# Lux_Meter.net
KiCad netlist of a schematic drawn in EAGLE
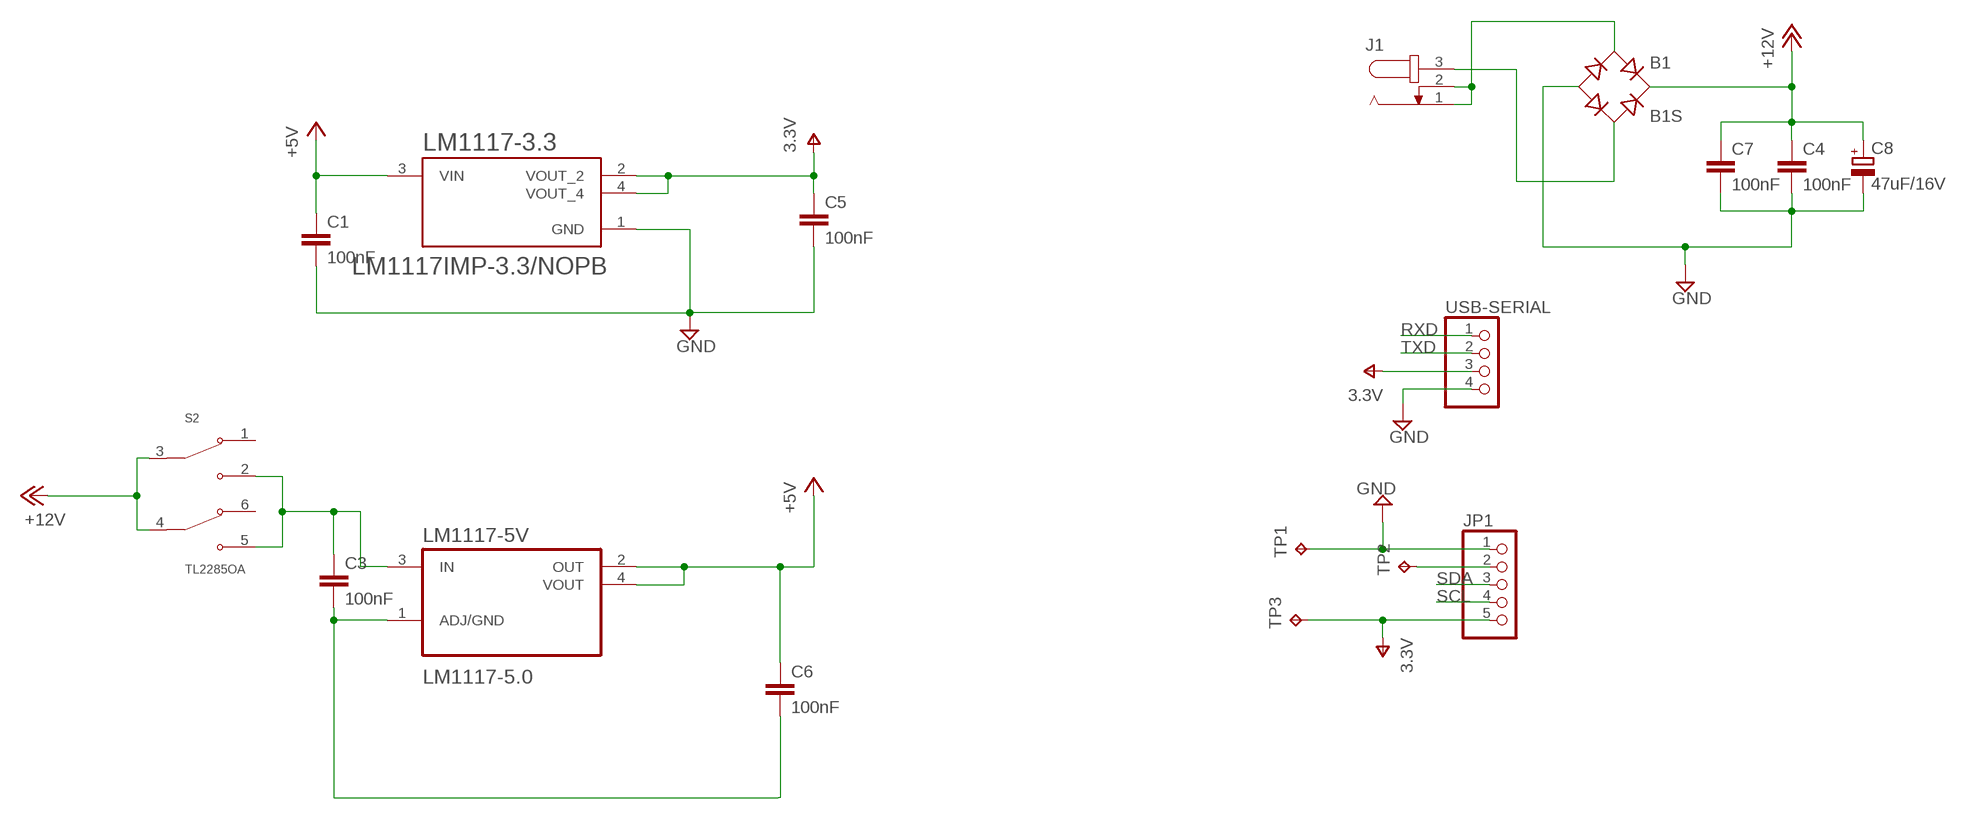
[diagram p0: schematic, sheet 1]
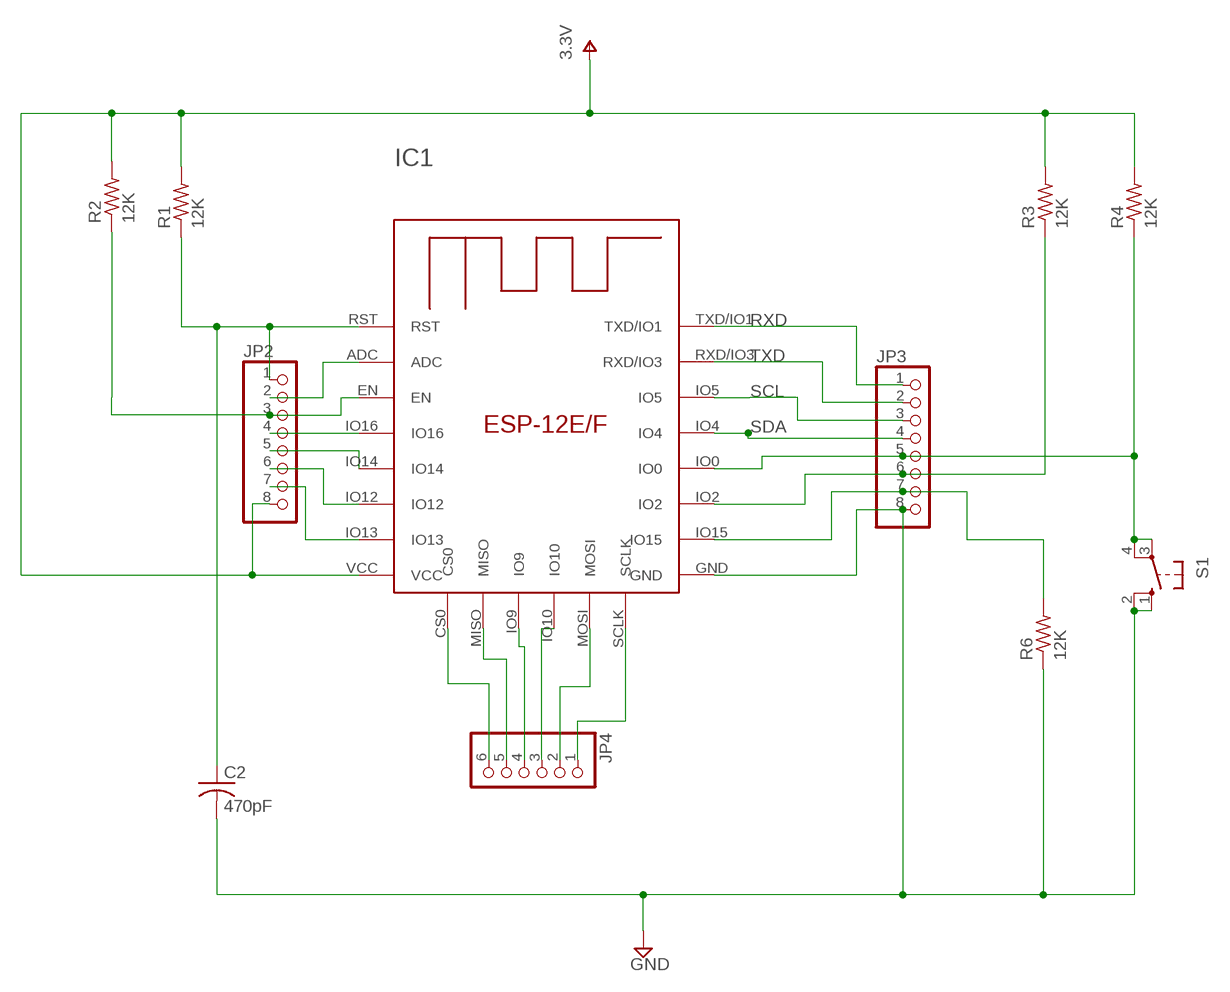
[diagram p1: schematic, sheet 2]

(export (version "E")
  (design (tool "Eeschema 10.0.6"))
  (components
    (comp (ref "C2")
      (value "470pF")
      (footprint "eagle-import:C0805")
      (libsource (lib "eagle-import") (part "C-USC0805"))
    )
    (comp (ref "IC1")
      (value "ESP-12E/F")
      (footprint "eagle-import:ESP-12E")
      (libsource (lib "eagle-import") (part "ESP-12E/F"))
    )
    (comp (ref "JP2")
      (value "PINHD-1X8")
      (footprint "eagle-import:1X08")
      (libsource (lib "eagle-import") (part "PINHD-1X8"))
    )
    (comp (ref "JP3")
      (value "PINHD-1X8")
      (footprint "eagle-import:1X08")
      (libsource (lib "eagle-import") (part "PINHD-1X8"))
    )
    (comp (ref "JP4")
      (value "PINHD-1X6")
      (footprint "eagle-import:1X06")
      (libsource (lib "eagle-import") (part "PINHD-1X6"))
    )
    (comp (ref "R1")
      (value "12K")
      (footprint "eagle-import:R0805")
      (libsource (lib "eagle-import") (part "R-US_R0805"))
    )
    (comp (ref "R2")
      (value "12K")
      (footprint "eagle-import:R0805")
      (libsource (lib "eagle-import") (part "R-US_R0805"))
    )
    (comp (ref "R3")
      (value "12K")
      (footprint "eagle-import:R0805")
      (libsource (lib "eagle-import") (part "R-US_R0805"))
    )
    (comp (ref "R4")
      (value "12K")
      (footprint "eagle-import:R0805")
      (libsource (lib "eagle-import") (part "R-US_R0805"))
    )
    (comp (ref "R6")
      (value "12K")
      (footprint "eagle-import:R0805")
      (libsource (lib "eagle-import") (part "R-US_R0805"))
    )
    (comp (ref "S1")
      (value "10-XX")
      (footprint "eagle-import:B3F-10XX")
      (fields (field (name "MPN") "B3F-1000"))
      (libsource (lib "eagle-import") (part "10-XX"))
    )
    (comp (ref "B1")
      (value "B1S")
      (footprint "eagle-import:MBS")
      (libsource (lib "eagle-import") (part "BS1"))
    )
    (comp (ref "C1")
      (value "100nF")
      (footprint "eagle-import:C0603K")
      (libsource (lib "eagle-import") (part "C-EUC0603K"))
    )
    (comp (ref "C3")
      (value "100nF")
      (footprint "eagle-import:C0603K")
      (libsource (lib "eagle-import") (part "C-EUC0603K"))
    )
    (comp (ref "C4")
      (value "100nF")
      (footprint "eagle-import:C0603K")
      (libsource (lib "eagle-import") (part "C-EUC0603K"))
    )
    (comp (ref "C5")
      (value "100nF")
      (footprint "eagle-import:C0805K")
      (libsource (lib "eagle-import") (part "C-EUC0805K"))
    )
    (comp (ref "C6")
      (value "100nF")
      (footprint "eagle-import:C0805K")
      (libsource (lib "eagle-import") (part "C-EUC0805K"))
    )
    (comp (ref "C7")
      (value "100nF")
      (footprint "eagle-import:C0805K")
      (libsource (lib "eagle-import") (part "C-EUC0805K"))
    )
    (comp (ref "C8")
      (value "47uF/16V")
      (footprint "eagle-import:C_6032-28R")
      (libsource (lib "eagle-import") (part "CPOL-EUC/6032-28R"))
    )
    (comp (ref "J1")
      (value "JACK-PLUG0")
      (footprint "eagle-import:SPC4077")
      (libsource (lib "eagle-import") (part "JACK-PLUG0"))
    )
    (comp (ref "JP1")
      (value "PINHD-1X5")
      (footprint "eagle-import:1X05")
      (libsource (lib "eagle-import") (part "PINHD-1X5"))
    )
    (comp (ref "LM1117-3.3")
      (value "LM1117IMP-3.3/NOPB")
      (footprint "eagle-import:VREG_LM1117IMP-3.3_NOPB")
      (fields (field (name "MF") "Texas"))
      (libsource (lib "eagle-import") (part "LM1117IMP-3.3/NOPB"))
    )
    (comp (ref "LM1117-5V")
      (value "LM1117-5.0")
      (footprint "eagle-import:SOT230P700X180-4N")
      (fields (field (name "MF") "Texas Instruments") (field (name "MP") "LM1117MP-5.0/NOPB"))
      (libsource (lib "eagle-import") (part "LM1117MP-5.0"))
    )
    (comp (ref "S2")
      (value "TL2285OA")
      (footprint "eagle-import:SW_TL2285OA")
      (fields (field (name "MF") "E-Switch"))
      (libsource (lib "eagle-import") (part "TL2285OA"))
    )
    (comp (ref "TP1")
      (value "TPTP13SQ")
      (footprint "eagle-import:TP13SQ")
      (libsource (lib "eagle-import") (part "TPTP13SQ"))
    )
    (comp (ref "TP2")
      (value "TPTP13SQ")
      (footprint "eagle-import:TP13SQ")
      (libsource (lib "eagle-import") (part "TPTP13SQ"))
    )
    (comp (ref "TP3")
      (value "TPTP13SQ")
      (footprint "eagle-import:TP13SQ")
      (libsource (lib "eagle-import") (part "TPTP13SQ"))
    )
    (comp (ref "USB-SERIAL")
      (value "PINHD-1X4")
      (footprint "eagle-import:1X04")
      (libsource (lib "eagle-import") (part "PINHD-1X4"))
    )
  )
  (nets
    (net (code "1") (name "+5V") (class "Default")
      (node (ref "C1") (pin "1") (pinfunction "1_1") (pintype "passive"))
      (node (ref "C6") (pin "1") (pinfunction "1_1") (pintype "passive"))
      (node (ref "LM1117-3.3") (pin "3") (pinfunction "VIN_3") (pintype "input"))
      (node (ref "LM1117-5V") (pin "2") (pinfunction "OUT_2") (pintype "output"))
      (node (ref "LM1117-5V") (pin "4") (pinfunction "VOUT_4") (pintype "output"))
    )
    (net (code "2") (name "+12V") (class "Default")
      (node (ref "B1") (pin "+") (pinfunction "+_+") (pintype "passive"))
      (node (ref "C4") (pin "1") (pinfunction "1_1") (pintype "passive"))
      (node (ref "C7") (pin "1") (pinfunction "1_1") (pintype "passive"))
      (node (ref "C8") (pin "+") (pinfunction "+_+") (pintype "passive"))
      (node (ref "S2") (pin "3") (pinfunction "COM1_3") (pintype "passive"))
      (node (ref "S2") (pin "4") (pinfunction "COM2_4") (pintype "passive"))
    )
    (net (code "3") (name "GND") (class "Default")
      (node (ref "B1") (pin "-") (pinfunction "-_-") (pintype "passive"))
      (node (ref "C1") (pin "2") (pinfunction "2_2") (pintype "passive"))
      (node (ref "C2") (pin "2") (pinfunction "2_2") (pintype "passive"))
      (node (ref "C4") (pin "2") (pinfunction "2_2") (pintype "passive"))
      (node (ref "C5") (pin "2") (pinfunction "2_2") (pintype "passive"))
      (node (ref "C7") (pin "2") (pinfunction "2_2") (pintype "passive"))
      (node (ref "C8") (pin "-") (pinfunction "-_-") (pintype "passive"))
      (node (ref "IC1") (pin "GND") (pinfunction "GND_GND") (pintype "power_in"))
      (node (ref "JP1") (pin "1") (pinfunction "1_1") (pintype "passive"))
      (node (ref "JP3") (pin "8") (pinfunction "8_8") (pintype "passive"))
      (node (ref "LM1117-3.3") (pin "1") (pinfunction "GND_1") (pintype "power_in"))
      (node (ref "R6") (pin "1") (pinfunction "1_1") (pintype "passive"))
      (node (ref "S1") (pin "1") (pinfunction "S_1") (pintype "passive"))
      (node (ref "S1") (pin "2") (pinfunction "S1_2") (pintype "passive"))
      (node (ref "TP1") (pin "TP") (pinfunction "TP_TP") (pintype "input"))
      (node (ref "USB-SERIAL") (pin "4") (pinfunction "4_4") (pintype "passive"))
    )
    (net (code "4") (name "Net-(B1-PadAC1)") (class "Default")
      (node (ref "B1") (pin "AC1") (pinfunction "AC1_AC1") (pintype "passive"))
      (node (ref "J1") (pin "1") (pinfunction "1_1") (pintype "passive"))
      (node (ref "J1") (pin "2") (pinfunction "2_2") (pintype "passive"))
    )
    (net (code "5") (name "Net-(B1-PadAC2)") (class "Default")
      (node (ref "B1") (pin "AC2") (pinfunction "AC2_AC2") (pintype "passive"))
      (node (ref "J1") (pin "3") (pinfunction "3_3") (pintype "passive"))
    )
    (net (code "6") (name "Net-(C2-Pad1)") (class "Default")
      (node (ref "C2") (pin "1") (pinfunction "1_1") (pintype "passive"))
      (node (ref "IC1") (pin "RST") (pinfunction "RST_RST") (pintype "input"))
      (node (ref "JP2") (pin "1") (pinfunction "1_1") (pintype "passive"))
      (node (ref "R1") (pin "1") (pinfunction "1_1") (pintype "passive"))
    )
    (net (code "7") (name "Net-(IC1-PadADC)") (class "Default")
      (node (ref "IC1") (pin "ADC") (pinfunction "ADC_ADC") (pintype "bidirectional"))
      (node (ref "JP2") (pin "2") (pinfunction "2_2") (pintype "passive"))
    )
    (net (code "8") (name "Net-(IC1-PadCS0)") (class "Default")
      (node (ref "IC1") (pin "CS0") (pinfunction "CS0_CS0") (pintype "bidirectional"))
      (node (ref "JP4") (pin "6") (pinfunction "6_6") (pintype "passive"))
    )
    (net (code "9") (name "Net-(IC1-PadEN)") (class "Default")
      (node (ref "IC1") (pin "EN") (pinfunction "EN_EN") (pintype "bidirectional"))
      (node (ref "JP2") (pin "3") (pinfunction "3_3") (pintype "passive"))
      (node (ref "R2") (pin "1") (pinfunction "1_1") (pintype "passive"))
    )
    (net (code "10") (name "Net-(IC1-PadIO2)") (class "Default")
      (node (ref "IC1") (pin "IO2") (pinfunction "IO2_IO2") (pintype "bidirectional"))
      (node (ref "JP3") (pin "6") (pinfunction "6_6") (pintype "passive"))
      (node (ref "R3") (pin "1") (pinfunction "1_1") (pintype "passive"))
    )
    (net (code "11") (name "Net-(IC1-PadIO9)") (class "Default")
      (node (ref "IC1") (pin "IO9") (pinfunction "IO9_IO9") (pintype "bidirectional"))
      (node (ref "JP4") (pin "4") (pinfunction "4_4") (pintype "passive"))
    )
    (net (code "12") (name "Net-(IC1-PadIO10)") (class "Default")
      (node (ref "IC1") (pin "IO10") (pinfunction "IO10_IO10") (pintype "bidirectional"))
      (node (ref "JP4") (pin "3") (pinfunction "3_3") (pintype "passive"))
    )
    (net (code "13") (name "Net-(IC1-PadIO12)") (class "Default")
      (node (ref "IC1") (pin "IO12") (pinfunction "IO12_IO12") (pintype "bidirectional"))
      (node (ref "JP2") (pin "6") (pinfunction "6_6") (pintype "passive"))
    )
    (net (code "14") (name "Net-(IC1-PadIO13)") (class "Default")
      (node (ref "IC1") (pin "IO13") (pinfunction "IO13_IO13") (pintype "bidirectional"))
      (node (ref "JP2") (pin "7") (pinfunction "7_7") (pintype "passive"))
    )
    (net (code "15") (name "Net-(IC1-PadIO14)") (class "Default")
      (node (ref "IC1") (pin "IO14") (pinfunction "IO14_IO14") (pintype "bidirectional"))
      (node (ref "JP2") (pin "5") (pinfunction "5_5") (pintype "passive"))
    )
    (net (code "16") (name "Net-(IC1-PadIO15)") (class "Default")
      (node (ref "IC1") (pin "IO15") (pinfunction "IO15_IO15") (pintype "bidirectional"))
      (node (ref "JP3") (pin "7") (pinfunction "7_7") (pintype "passive"))
      (node (ref "R6") (pin "2") (pinfunction "2_2") (pintype "passive"))
    )
    (net (code "17") (name "Net-(IC1-PadIO16)") (class "Default")
      (node (ref "IC1") (pin "IO16") (pinfunction "IO16_IO16") (pintype "bidirectional"))
      (node (ref "JP2") (pin "4") (pinfunction "4_4") (pintype "passive"))
    )
    (net (code "18") (name "Net-(IC1-PadMISO)") (class "Default")
      (node (ref "IC1") (pin "MISO") (pinfunction "MISO_MISO") (pintype "bidirectional"))
      (node (ref "JP4") (pin "5") (pinfunction "5_5") (pintype "passive"))
    )
    (net (code "19") (name "Net-(IC1-PadMOSI)") (class "Default")
      (node (ref "IC1") (pin "MOSI") (pinfunction "MOSI_MOSI") (pintype "bidirectional"))
      (node (ref "JP4") (pin "2") (pinfunction "2_2") (pintype "passive"))
    )
    (net (code "20") (name "Net-(IC1-PadSCLK)") (class "Default")
      (node (ref "IC1") (pin "SCLK") (pinfunction "SCLK_SCLK") (pintype "bidirectional"))
      (node (ref "JP4") (pin "1") (pinfunction "1_1") (pintype "passive"))
    )
    (net (code "21") (name "Net-(JP1-Pad2)") (class "Default")
      (node (ref "JP1") (pin "2") (pinfunction "2_2") (pintype "passive"))
      (node (ref "TP2") (pin "TP") (pinfunction "TP_TP") (pintype "input"))
    )
    (net (code "22") (name "Net-(LM1117-5V-ADJ{slash}GND)") (class "Default")
      (node (ref "C3") (pin "2") (pinfunction "2_2") (pintype "passive"))
      (node (ref "C6") (pin "2") (pinfunction "2_2") (pintype "passive"))
      (node (ref "LM1117-5V") (pin "1") (pinfunction "ADJ/GND_1") (pintype "bidirectional"))
    )
    (net (code "23") (name "Net-(LM1117-5V-IN)") (class "Default")
      (node (ref "C3") (pin "1") (pinfunction "1_1") (pintype "passive"))
      (node (ref "LM1117-5V") (pin "3") (pinfunction "IN_3") (pintype "input"))
      (node (ref "S2") (pin "2") (pinfunction "NO1_2") (pintype "passive"))
      (node (ref "S2") (pin "5") (pinfunction "NO2_5") (pintype "passive"))
    )
    (net (code "24") (name "Net-(S1-P)") (class "Default")
      (node (ref "IC1") (pin "IO0") (pinfunction "IO0_IO0") (pintype "bidirectional"))
      (node (ref "JP3") (pin "5") (pinfunction "5_5") (pintype "passive"))
      (node (ref "R4") (pin "1") (pinfunction "1_1") (pintype "passive"))
      (node (ref "S1") (pin "3") (pinfunction "P_3") (pintype "passive"))
      (node (ref "S1") (pin "4") (pinfunction "P1_4") (pintype "passive"))
    )
    (net (code "25") (name "RXD") (class "Default")
      (node (ref "IC1") (pin "TXD/IO1") (pinfunction "TXD/IO1_TXD/IO1") (pintype "bidirectional"))
      (node (ref "JP3") (pin "1") (pinfunction "1_1") (pintype "passive"))
      (node (ref "USB-SERIAL") (pin "1") (pinfunction "1_1") (pintype "passive"))
    )
    (net (code "26") (name "SCL") (class "Default")
      (node (ref "IC1") (pin "IO5") (pinfunction "IO5_IO5") (pintype "bidirectional"))
      (node (ref "JP1") (pin "4") (pinfunction "4_4") (pintype "passive"))
      (node (ref "JP3") (pin "3") (pinfunction "3_3") (pintype "passive"))
    )
    (net (code "27") (name "SDA") (class "Default")
      (node (ref "IC1") (pin "IO4") (pinfunction "IO4_IO4") (pintype "bidirectional"))
      (node (ref "JP1") (pin "3") (pinfunction "3_3") (pintype "passive"))
      (node (ref "JP3") (pin "4") (pinfunction "4_4") (pintype "passive"))
    )
    (net (code "28") (name "TXD") (class "Default")
      (node (ref "IC1") (pin "RXD/IO3") (pinfunction "RXD/IO3_RXD/IO3") (pintype "bidirectional"))
      (node (ref "JP3") (pin "2") (pinfunction "2_2") (pintype "passive"))
      (node (ref "USB-SERIAL") (pin "2") (pinfunction "2_2") (pintype "passive"))
    )
    (net (code "29") (name "V+") (class "Default")
      (node (ref "C5") (pin "1") (pinfunction "1_1") (pintype "passive"))
      (node (ref "IC1") (pin "VCC") (pinfunction "VCC_VCC") (pintype "power_in"))
      (node (ref "JP1") (pin "5") (pinfunction "5_5") (pintype "passive"))
      (node (ref "JP2") (pin "8") (pinfunction "8_8") (pintype "passive"))
      (node (ref "LM1117-3.3") (pin "2") (pinfunction "VOUT_2_2") (pintype "output"))
      (node (ref "LM1117-3.3") (pin "4") (pinfunction "VOUT_4_4") (pintype "output"))
      (node (ref "R1") (pin "2") (pinfunction "2_2") (pintype "passive"))
      (node (ref "R2") (pin "2") (pinfunction "2_2") (pintype "passive"))
      (node (ref "R3") (pin "2") (pinfunction "2_2") (pintype "passive"))
      (node (ref "R4") (pin "2") (pinfunction "2_2") (pintype "passive"))
      (node (ref "TP3") (pin "TP") (pinfunction "TP_TP") (pintype "input"))
      (node (ref "USB-SERIAL") (pin "3") (pinfunction "3_3") (pintype "passive"))
    )
    (net (code "30") (name "unconnected-(S2-NC1-Pad1)") (class "Default")
      (node (ref "S2") (pin "1") (pinfunction "NC1_1") (pintype "passive"))
    )
    (net (code "31") (name "unconnected-(S2-NC2-Pad6)") (class "Default")
      (node (ref "S2") (pin "6") (pinfunction "NC2_6") (pintype "passive"))
    )
  )
)
